# cpod-MCP1700-AM2321.net
KiCad netlist of a schematic drawn in EAGLE
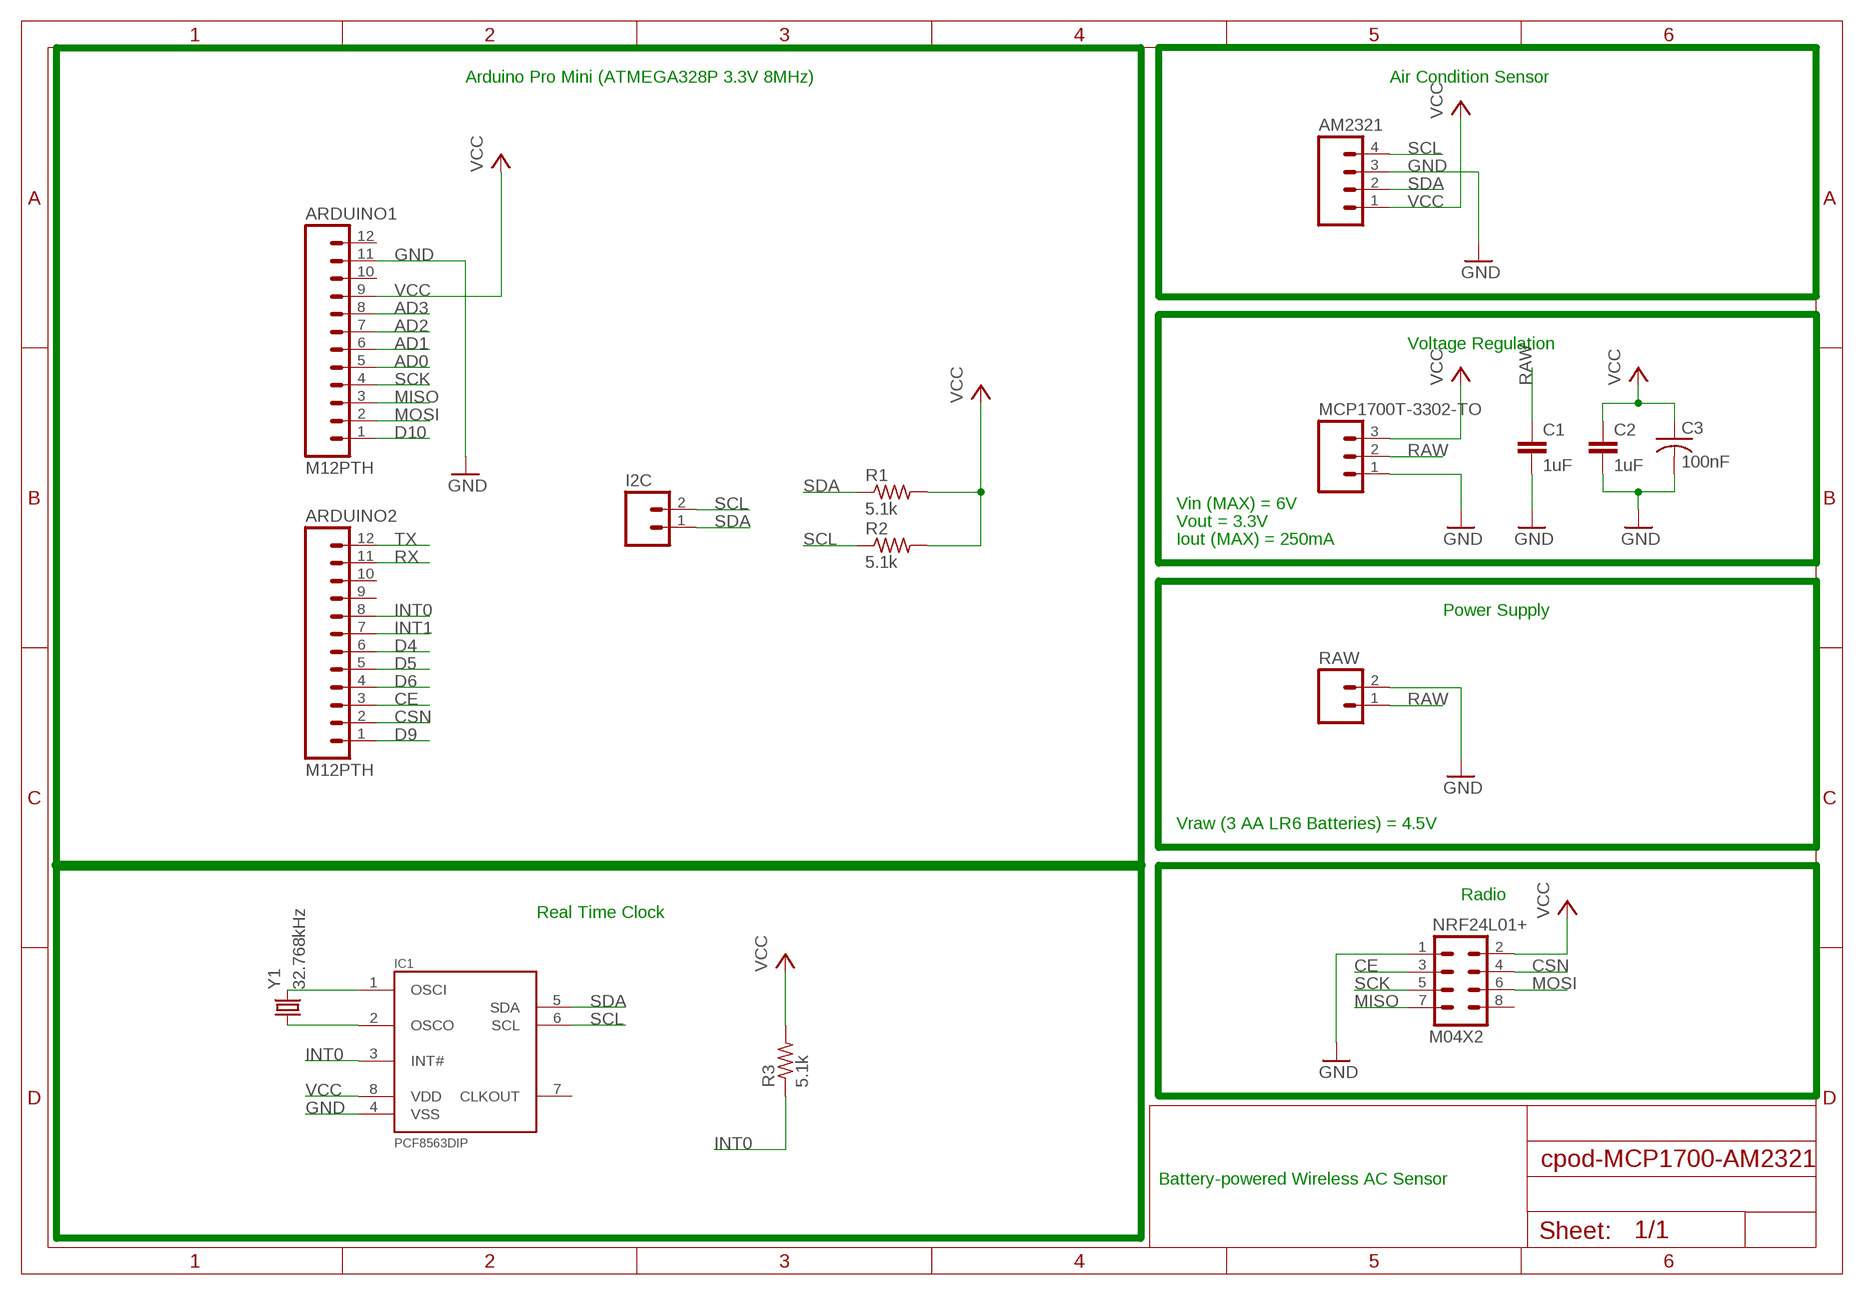
[diagram p0: schematic, sheet 1]

(export (version "E")
  (design (tool "Eeschema 10.0.6"))
  (components
    (comp (ref "AM2321")
      (value "M04PTH")
      (footprint "eagle-import:1X04")
      (libsource (lib "eagle-import") (part "M04PTH"))
    )
    (comp (ref "ARDUINO1")
      (value "M12PTH")
      (footprint "eagle-import:1X12")
      (libsource (lib "eagle-import") (part "M12PTH"))
    )
    (comp (ref "ARDUINO2")
      (value "M12PTH")
      (footprint "eagle-import:1X12")
      (libsource (lib "eagle-import") (part "M12PTH"))
    )
    (comp (ref "C1")
      (value "1uF")
      (footprint "eagle-import:CAP-PTH-SMALL")
      (libsource (lib "eagle-import") (part "CAPPTH"))
    )
    (comp (ref "C2")
      (value "1uF")
      (footprint "eagle-import:CAP-PTH-SMALL")
      (libsource (lib "eagle-import") (part "CAPPTH"))
    )
    (comp (ref "C3")
      (value "100nF")
      (footprint "eagle-import:C025-024X044")
      (libsource (lib "eagle-import") (part "C-US025-024X044"))
    )
    (comp (ref "I2C")
      (value "M02PTH")
      (footprint "eagle-import:1X02")
      (libsource (lib "eagle-import") (part "M02PTH"))
    )
    (comp (ref "IC1")
      (value "PCF8563DIP")
      (footprint "eagle-import:DIL08")
      (libsource (lib "eagle-import") (part "PCF8563DIP"))
    )
    (comp (ref "MCP1700T-3302-TO")
      (value "M03PTH")
      (footprint "eagle-import:1X03")
      (libsource (lib "eagle-import") (part "M03PTH"))
    )
    (comp (ref "NRF24L01+")
      (value "M04X2")
      (footprint "eagle-import:2X4")
      (libsource (lib "eagle-import") (part "M04X2"))
    )
    (comp (ref "R1")
      (value "5.1k")
      (footprint "eagle-import:0207_2V")
      (libsource (lib "eagle-import") (part "R-US_0207/2V"))
    )
    (comp (ref "R2")
      (value "5.1k")
      (footprint "eagle-import:0207_2V")
      (libsource (lib "eagle-import") (part "R-US_0207/2V"))
    )
    (comp (ref "R3")
      (value "5.1k")
      (footprint "eagle-import:0204_7")
      (libsource (lib "eagle-import") (part "R-US_0204/7"))
    )
    (comp (ref "RAW")
      (value "M02PTH")
      (footprint "eagle-import:1X02")
      (libsource (lib "eagle-import") (part "M02PTH"))
    )
    (comp (ref "Y1")
      (value "32.768kHz")
      (footprint "eagle-import:TC26H")
      (libsource (lib "eagle-import") (part "CRYSTALTC26H"))
    )
  )
  (nets
    (net (code "1") (name "/AD0") (class "Default")
      (node (ref "ARDUINO1") (pin "5") (pinfunction "5_5") (pintype "passive"))
    )
    (net (code "2") (name "/AD1") (class "Default")
      (node (ref "ARDUINO1") (pin "6") (pinfunction "6_6") (pintype "passive"))
    )
    (net (code "3") (name "/AD2") (class "Default")
      (node (ref "ARDUINO1") (pin "7") (pinfunction "7_7") (pintype "passive"))
    )
    (net (code "4") (name "/AD3") (class "Default")
      (node (ref "ARDUINO1") (pin "8") (pinfunction "8_8") (pintype "passive"))
    )
    (net (code "5") (name "/CE") (class "Default")
      (node (ref "ARDUINO2") (pin "3") (pinfunction "3_3") (pintype "passive"))
      (node (ref "NRF24L01+") (pin "3") (pinfunction "3_3") (pintype "passive"))
    )
    (net (code "6") (name "/CSN") (class "Default")
      (node (ref "ARDUINO2") (pin "2") (pinfunction "2_2") (pintype "passive"))
      (node (ref "NRF24L01+") (pin "4") (pinfunction "4_4") (pintype "passive"))
    )
    (net (code "7") (name "/D4") (class "Default")
      (node (ref "ARDUINO2") (pin "6") (pinfunction "6_6") (pintype "passive"))
    )
    (net (code "8") (name "/D5") (class "Default")
      (node (ref "ARDUINO2") (pin "5") (pinfunction "5_5") (pintype "passive"))
    )
    (net (code "9") (name "/D6") (class "Default")
      (node (ref "ARDUINO2") (pin "4") (pinfunction "4_4") (pintype "passive"))
    )
    (net (code "10") (name "/D9") (class "Default")
      (node (ref "ARDUINO2") (pin "1") (pinfunction "1_1") (pintype "passive"))
    )
    (net (code "11") (name "/D10") (class "Default")
      (node (ref "ARDUINO1") (pin "1") (pinfunction "1_1") (pintype "passive"))
    )
    (net (code "12") (name "/INT0") (class "Default")
      (node (ref "ARDUINO2") (pin "8") (pinfunction "8_8") (pintype "passive"))
      (node (ref "IC1") (pin "3") (pinfunction "INT#_3") (pintype "bidirectional"))
      (node (ref "R3") (pin "1") (pinfunction "1_1") (pintype "passive"))
    )
    (net (code "13") (name "/INT1") (class "Default")
      (node (ref "ARDUINO2") (pin "7") (pinfunction "7_7") (pintype "passive"))
    )
    (net (code "14") (name "/MISO") (class "Default")
      (node (ref "ARDUINO1") (pin "3") (pinfunction "3_3") (pintype "passive"))
      (node (ref "NRF24L01+") (pin "7") (pinfunction "7_7") (pintype "passive"))
    )
    (net (code "15") (name "/MOSI") (class "Default")
      (node (ref "ARDUINO1") (pin "2") (pinfunction "2_2") (pintype "passive"))
      (node (ref "NRF24L01+") (pin "6") (pinfunction "6_6") (pintype "passive"))
    )
    (net (code "16") (name "/RAW") (class "Default")
      (node (ref "C1") (pin "1") (pinfunction "1_1") (pintype "passive"))
      (node (ref "MCP1700T-3302-TO") (pin "2") (pinfunction "2_2") (pintype "passive"))
      (node (ref "RAW") (pin "1") (pinfunction "1_1") (pintype "passive"))
    )
    (net (code "17") (name "/RX") (class "Default")
      (node (ref "ARDUINO2") (pin "11") (pinfunction "11_11") (pintype "passive"))
    )
    (net (code "18") (name "/SCK") (class "Default")
      (node (ref "ARDUINO1") (pin "4") (pinfunction "4_4") (pintype "passive"))
      (node (ref "NRF24L01+") (pin "5") (pinfunction "5_5") (pintype "passive"))
    )
    (net (code "19") (name "/SCL") (class "Default")
      (node (ref "AM2321") (pin "4") (pinfunction "4_4") (pintype "passive"))
      (node (ref "I2C") (pin "2") (pinfunction "2_2") (pintype "passive"))
      (node (ref "IC1") (pin "6") (pinfunction "SCL_6") (pintype "bidirectional"))
      (node (ref "R2") (pin "1") (pinfunction "1_1") (pintype "passive"))
    )
    (net (code "20") (name "/SDA") (class "Default")
      (node (ref "AM2321") (pin "2") (pinfunction "2_2") (pintype "passive"))
      (node (ref "I2C") (pin "1") (pinfunction "1_1") (pintype "passive"))
      (node (ref "IC1") (pin "5") (pinfunction "SDA_5") (pintype "bidirectional"))
      (node (ref "R1") (pin "1") (pinfunction "1_1") (pintype "passive"))
    )
    (net (code "21") (name "/TX") (class "Default")
      (node (ref "ARDUINO2") (pin "12") (pinfunction "12_12") (pintype "passive"))
    )
    (net (code "22") (name "GND") (class "Default")
      (node (ref "AM2321") (pin "3") (pinfunction "3_3") (pintype "passive"))
      (node (ref "ARDUINO1") (pin "11") (pinfunction "11_11") (pintype "passive"))
      (node (ref "C1") (pin "2") (pinfunction "2_2") (pintype "passive"))
      (node (ref "C2") (pin "2") (pinfunction "2_2") (pintype "passive"))
      (node (ref "C3") (pin "2") (pinfunction "2_2") (pintype "passive"))
      (node (ref "IC1") (pin "4") (pinfunction "VSS_4") (pintype "bidirectional"))
      (node (ref "MCP1700T-3302-TO") (pin "1") (pinfunction "1_1") (pintype "passive"))
      (node (ref "NRF24L01+") (pin "1") (pinfunction "1_1") (pintype "passive"))
      (node (ref "RAW") (pin "2") (pinfunction "2_2") (pintype "passive"))
    )
    (net (code "23") (name "Net-(IC1-OSCI)") (class "Default")
      (node (ref "IC1") (pin "1") (pinfunction "OSCI_1") (pintype "bidirectional"))
      (node (ref "Y1") (pin "2") (pinfunction "2_2") (pintype "passive"))
    )
    (net (code "24") (name "Net-(IC1-OSCO)") (class "Default")
      (node (ref "IC1") (pin "2") (pinfunction "OSCO_2") (pintype "bidirectional"))
      (node (ref "Y1") (pin "1") (pinfunction "1_1") (pintype "passive"))
    )
    (net (code "25") (name "VCC") (class "Default")
      (node (ref "AM2321") (pin "1") (pinfunction "1_1") (pintype "passive"))
      (node (ref "ARDUINO1") (pin "9") (pinfunction "9_9") (pintype "passive"))
      (node (ref "C2") (pin "1") (pinfunction "1_1") (pintype "passive"))
      (node (ref "C3") (pin "1") (pinfunction "1_1") (pintype "passive"))
      (node (ref "IC1") (pin "8") (pinfunction "VDD_8") (pintype "bidirectional"))
      (node (ref "MCP1700T-3302-TO") (pin "3") (pinfunction "3_3") (pintype "passive"))
      (node (ref "NRF24L01+") (pin "2") (pinfunction "2_2") (pintype "passive"))
      (node (ref "R1") (pin "2") (pinfunction "2_2") (pintype "passive"))
      (node (ref "R2") (pin "2") (pinfunction "2_2") (pintype "passive"))
      (node (ref "R3") (pin "2") (pinfunction "2_2") (pintype "passive"))
    )
    (net (code "26") (name "unconnected-(ARDUINO1-Pad10)") (class "Default")
      (node (ref "ARDUINO1") (pin "10") (pinfunction "10_10") (pintype "passive"))
    )
    (net (code "27") (name "unconnected-(ARDUINO1-Pad12)") (class "Default")
      (node (ref "ARDUINO1") (pin "12") (pinfunction "12_12") (pintype "passive"))
    )
    (net (code "28") (name "unconnected-(ARDUINO2-Pad9)") (class "Default")
      (node (ref "ARDUINO2") (pin "9") (pinfunction "9_9") (pintype "passive"))
    )
    (net (code "29") (name "unconnected-(ARDUINO2-Pad10)") (class "Default")
      (node (ref "ARDUINO2") (pin "10") (pinfunction "10_10") (pintype "passive"))
    )
    (net (code "30") (name "unconnected-(IC1-CLKOUT-Pad7)") (class "Default")
      (node (ref "IC1") (pin "7") (pinfunction "CLKOUT_7") (pintype "bidirectional"))
    )
    (net (code "31") (name "unconnected-(NRF24L01+-Pad8)") (class "Default")
      (node (ref "NRF24L01+") (pin "8") (pinfunction "8_8") (pintype "passive"))
    )
  )
)
